# CMRI-Bus-Interface.net
KiCad netlist of a schematic drawn in EAGLE
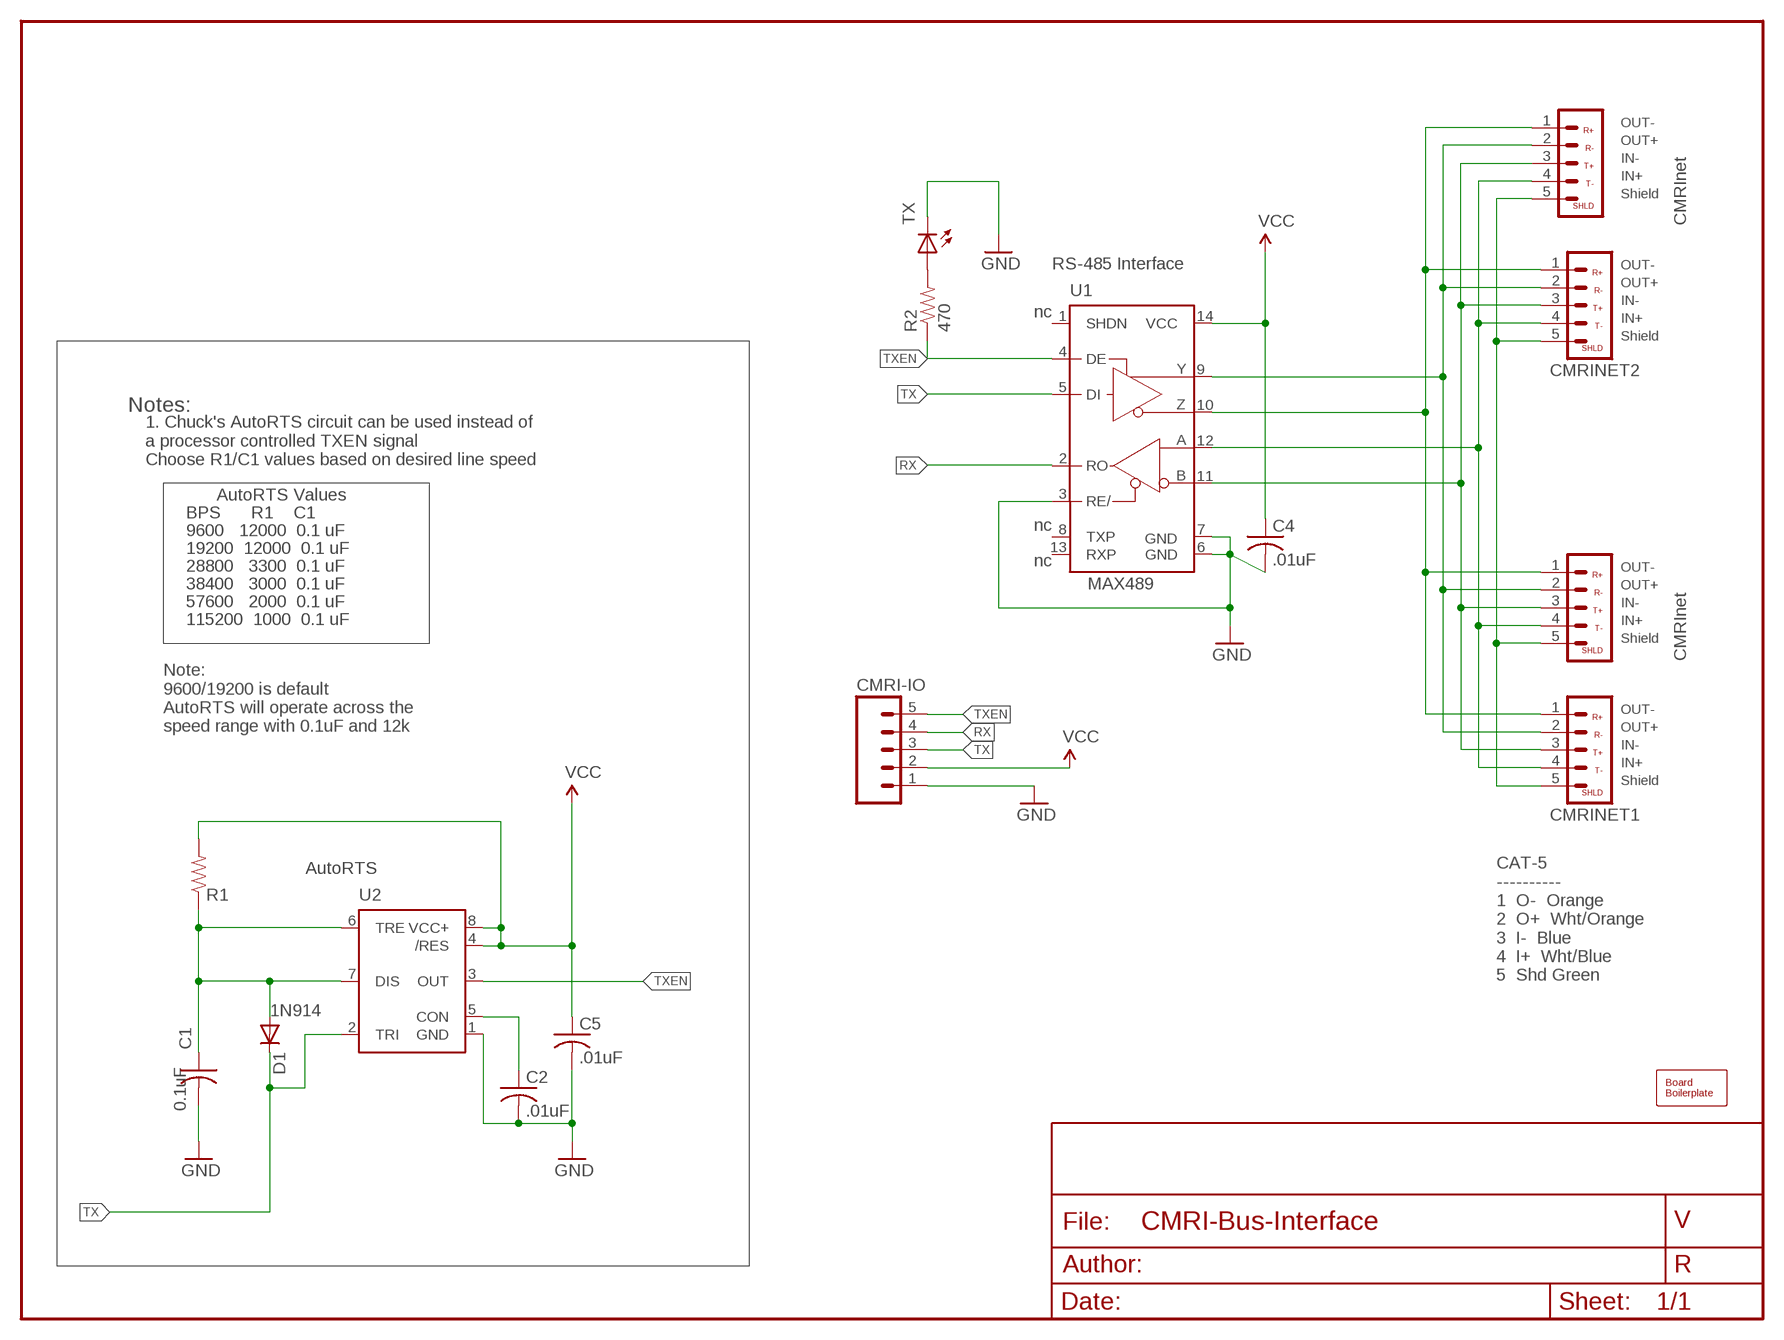
[diagram p0: schematic, sheet 1]

(export (version "E")
  (design (tool "Eeschema 10.0.6"))
  (components
    (comp (ref "BOARD1")
      (value "BOARD69X70")
      (footprint "eagle-import:BOARD-DINRAIL-2.7IN-7CM")
      (libsource (lib "eagle-import") (part "BOARD69X70"))
    )
    (comp (ref "C1")
      (value "0.1uF")
      (footprint "eagle-import:C050-024X044")
      (libsource (lib "eagle-import") (part "CAPPTH1"))
    )
    (comp (ref "C2")
      (value ".01uF")
      (footprint "eagle-import:C050-024X044")
      (libsource (lib "eagle-import") (part "CAPPTH1"))
    )
    (comp (ref "C4")
      (value ".01uF")
      (footprint "eagle-import:C-PTH-0.100")
      (libsource (lib "eagle-import") (part "CAPPTH2"))
    )
    (comp (ref "C5")
      (value ".01uF")
      (footprint "eagle-import:C-PTH-0.100")
      (libsource (lib "eagle-import") (part "CAPPTH2"))
    )
    (comp (ref "CMRI-IO")
      (value "CONNECTOR-M05CMRI")
      (footprint "eagle-import:CON-CMRI-IO")
      (libsource (lib "eagle-import") (part "CONNECTOR-M05CMRI"))
    )
    (comp (ref "CMRINET1")
      (value "CMRInet")
      (footprint "eagle-import:CMRINET-3.5MM")
      (libsource (lib "eagle-import") (part "CONNECTOR-CMRINET3.5MM"))
    )
    (comp (ref "CMRINET2")
      (value "CMRInet")
      (footprint "eagle-import:CMRINET-3.5MM")
      (libsource (lib "eagle-import") (part "CONNECTOR-CMRINET3.5MM"))
    )
    (comp (ref "CMRINET3")
      (value "CMRInet")
      (footprint "eagle-import:KK-156-5")
      (libsource (lib "eagle-import") (part "CONNECTOR-CMRINET.156"))
    )
    (comp (ref "CMRINET4")
      (value "CMRInet")
      (footprint "eagle-import:KK-156-5")
      (libsource (lib "eagle-import") (part "CONNECTOR-CMRINET.156"))
    )
    (comp (ref "D1")
      (value "1N4148")
      (footprint "eagle-import:DIODE-1N4148")
      (libsource (lib "eagle-import") (part "DIODE1N4148"))
    )
    (comp (ref "R1")
      (value "RPTH03")
      (footprint "eagle-import:AXIAL-0.3-RES")
      (libsource (lib "eagle-import") (part "RPTH03"))
    )
    (comp (ref "R2")
      (value "470")
      (footprint "eagle-import:AXIAL-0.3-RES")
      (libsource (lib "eagle-import") (part "RPTH03"))
    )
    (comp (ref "TX")
      (value "LEDLED5MM")
      (footprint "eagle-import:LED5MM")
      (libsource (lib "eagle-import") (part "LEDLED5MM"))
    )
    (comp (ref "U1")
      (value "MAX3465CPD")
      (footprint "eagle-import:DIL14")
      (fields (field (name "MPN") "MAX3465CPD+"))
      (libsource (lib "eagle-import") (part "MAX346PD5C"))
    )
    (comp (ref "U2")
      (value "NE555P")
      (footprint "eagle-import:DIL-08")
      (fields (field (name "MF") "Arrow Electronics") (field (name "MPN") "NE555N"))
      (libsource (lib "eagle-import") (part "NE555P"))
    )
  )
  (nets
    (net (code "1") (name "GND") (class "Default")
      (node (ref "C1") (pin "2") (pinfunction "2_2") (pintype "passive"))
      (node (ref "C2") (pin "2") (pinfunction "2_2") (pintype "passive"))
      (node (ref "C4") (pin "2") (pinfunction "2_2") (pintype "passive"))
      (node (ref "C5") (pin "2") (pinfunction "2_2") (pintype "passive"))
      (node (ref "CMRI-IO") (pin "1") (pinfunction "1_1") (pintype "passive"))
      (node (ref "TX") (pin "K") (pinfunction "C_K") (pintype "passive"))
      (node (ref "U1") (pin "3") (pinfunction "RE/_3") (pintype "input"))
      (node (ref "U1") (pin "6") (pinfunction "GND_6") (pintype "power_in"))
      (node (ref "U1") (pin "7") (pinfunction "GND_7") (pintype "power_in"))
      (node (ref "U2") (pin "1") (pinfunction "GND_1") (pintype "power_in"))
    )
    (net (code "2") (name "Net-(CMRINET1-Pad5)") (class "Default")
      (node (ref "CMRINET1") (pin "5") (pinfunction "5_5") (pintype "passive"))
      (node (ref "CMRINET2") (pin "5") (pinfunction "5_5") (pintype "passive"))
      (node (ref "CMRINET3") (pin "5") (pinfunction "5_5") (pintype "passive"))
      (node (ref "CMRINET4") (pin "5") (pinfunction "5_5") (pintype "passive"))
    )
    (net (code "3") (name "Net-(R1-1)") (class "Default")
      (node (ref "C1") (pin "1") (pinfunction "1_1") (pintype "passive"))
      (node (ref "D1") (pin "A") (pinfunction "A_A") (pintype "passive"))
      (node (ref "R1") (pin "P$1") (pinfunction "1_P$1") (pintype "passive"))
      (node (ref "U2") (pin "6") (pinfunction "TRE_6") (pintype "input"))
      (node (ref "U2") (pin "7") (pinfunction "DIS_7") (pintype "input"))
    )
    (net (code "4") (name "Net-(R2-2)") (class "Default")
      (node (ref "R2") (pin "P$2") (pinfunction "2_P$2") (pintype "passive"))
      (node (ref "TX") (pin "A") (pinfunction "A_A") (pintype "passive"))
    )
    (net (code "5") (name "Net-(U1-A)") (class "Default")
      (node (ref "CMRINET1") (pin "4") (pinfunction "4_4") (pintype "passive"))
      (node (ref "CMRINET2") (pin "4") (pinfunction "4_4") (pintype "passive"))
      (node (ref "CMRINET3") (pin "4") (pinfunction "4_4") (pintype "passive"))
      (node (ref "CMRINET4") (pin "4") (pinfunction "4_4") (pintype "passive"))
      (node (ref "U1") (pin "12") (pinfunction "A_12") (pintype "input"))
    )
    (net (code "6") (name "Net-(U1-B)") (class "Default")
      (node (ref "CMRINET1") (pin "3") (pinfunction "3_3") (pintype "passive"))
      (node (ref "CMRINET2") (pin "3") (pinfunction "3_3") (pintype "passive"))
      (node (ref "CMRINET3") (pin "3") (pinfunction "3_3") (pintype "passive"))
      (node (ref "CMRINET4") (pin "3") (pinfunction "3_3") (pintype "passive"))
      (node (ref "U1") (pin "11") (pinfunction "B_11") (pintype "input"))
    )
    (net (code "7") (name "Net-(U1-Y)") (class "Default")
      (node (ref "CMRINET1") (pin "2") (pinfunction "2_2") (pintype "passive"))
      (node (ref "CMRINET2") (pin "2") (pinfunction "2_2") (pintype "passive"))
      (node (ref "CMRINET3") (pin "2") (pinfunction "2_2") (pintype "passive"))
      (node (ref "CMRINET4") (pin "2") (pinfunction "2_2") (pintype "passive"))
      (node (ref "U1") (pin "9") (pinfunction "Y_9") (pintype "output"))
    )
    (net (code "8") (name "Net-(U1-Z)") (class "Default")
      (node (ref "CMRINET1") (pin "1") (pinfunction "1_1") (pintype "passive"))
      (node (ref "CMRINET2") (pin "1") (pinfunction "1_1") (pintype "passive"))
      (node (ref "CMRINET3") (pin "1") (pinfunction "1_1") (pintype "passive"))
      (node (ref "CMRINET4") (pin "1") (pinfunction "1_1") (pintype "passive"))
      (node (ref "U1") (pin "10") (pinfunction "Z_10") (pintype "output"))
    )
    (net (code "9") (name "Net-(U2-CON)") (class "Default")
      (node (ref "C2") (pin "1") (pinfunction "1_1") (pintype "passive"))
      (node (ref "U2") (pin "5") (pinfunction "CON_5") (pintype "input"))
    )
    (net (code "10") (name "RX") (class "Default")
      (node (ref "CMRI-IO") (pin "4") (pinfunction "4_4") (pintype "passive"))
      (node (ref "U1") (pin "2") (pinfunction "RO_2") (pintype "output"))
    )
    (net (code "11") (name "TX") (class "Default")
      (node (ref "CMRI-IO") (pin "3") (pinfunction "3_3") (pintype "passive"))
      (node (ref "D1") (pin "C") (pinfunction "C_C") (pintype "passive"))
      (node (ref "U1") (pin "5") (pinfunction "DI_5") (pintype "input"))
      (node (ref "U2") (pin "2") (pinfunction "TRI_2") (pintype "input"))
    )
    (net (code "12") (name "TXEN") (class "Default")
      (node (ref "CMRI-IO") (pin "5") (pinfunction "5_5") (pintype "passive"))
      (node (ref "R2") (pin "P$1") (pinfunction "1_P$1") (pintype "passive"))
      (node (ref "U1") (pin "4") (pinfunction "DE_4") (pintype "input"))
      (node (ref "U2") (pin "3") (pinfunction "OUT_3") (pintype "output"))
    )
    (net (code "13") (name "VCC") (class "Default")
      (node (ref "C4") (pin "1") (pinfunction "1_1") (pintype "passive"))
      (node (ref "C5") (pin "1") (pinfunction "1_1") (pintype "passive"))
      (node (ref "CMRI-IO") (pin "2") (pinfunction "2_2") (pintype "passive"))
      (node (ref "R1") (pin "P$2") (pinfunction "2_P$2") (pintype "passive"))
      (node (ref "U1") (pin "14") (pinfunction "VCC_14") (pintype "power_in"))
      (node (ref "U2") (pin "4") (pinfunction "/RES_4") (pintype "input"))
      (node (ref "U2") (pin "8") (pinfunction "VCC+_8") (pintype "power_in"))
    )
    (net (code "14") (name "unconnected-(U1-RXP-Pad13)") (class "Default")
      (node (ref "U1") (pin "13") (pinfunction "RXP_13") (pintype "passive"))
    )
    (net (code "15") (name "unconnected-(U1-SHDN-Pad1)") (class "Default")
      (node (ref "U1") (pin "1") (pinfunction "SHDN_1") (pintype "input"))
    )
    (net (code "16") (name "unconnected-(U1-TXP-Pad8)") (class "Default")
      (node (ref "U1") (pin "8") (pinfunction "TXP_8") (pintype "passive"))
    )
  )
)
